# Microcontroller_s_Prephirals_Sheet.net
KiCad netlist of a schematic drawn in Altium Designer
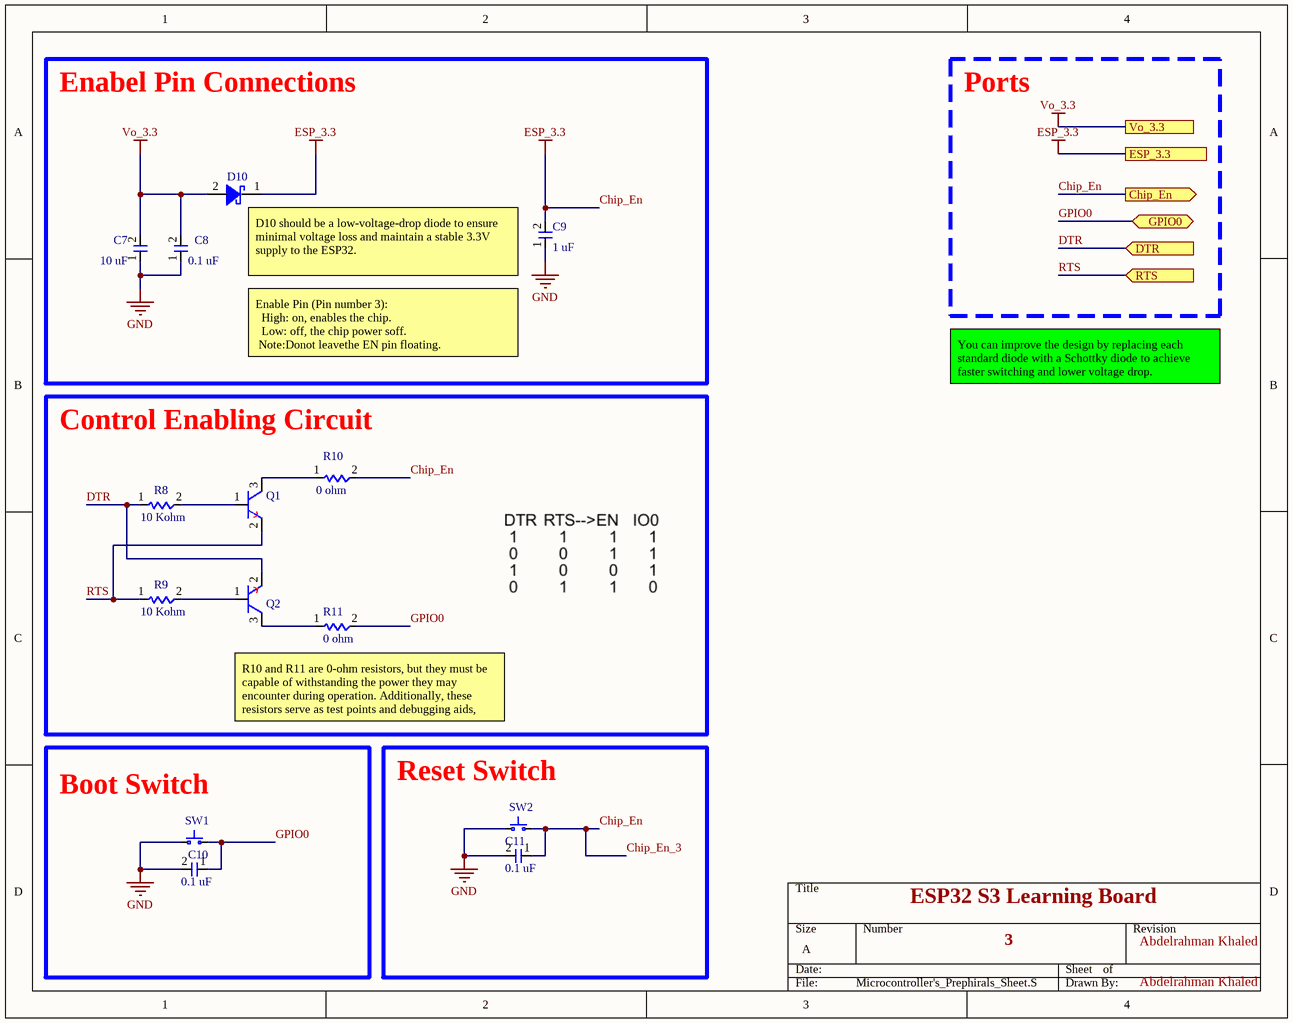
[diagram p0: Microcontroller's_Prephirals_Sheet.SchDoc]

(export (version "E")
  (design (tool "Eeschema 10.0.6"))
  (components
    (comp (ref "C7")
      (value "10 uF")
      (footprint "Capacitor")
      (libsource (lib "ESP32_S3_Integrated_Library") (part "Capacitor"))
    )
    (comp (ref "C8")
      (value "0.1 uF")
      (footprint "Capacitor")
      (libsource (lib "ESP32_S3_Integrated_Library") (part "Capacitor"))
    )
    (comp (ref "C9")
      (value "1 uF")
      (footprint "Capacitor")
      (libsource (lib "ESP32_S3_Integrated_Library") (part "Capacitor"))
    )
    (comp (ref "C10")
      (value "0.1 uF")
      (footprint "Capacitor")
      (libsource (lib "ESP32_S3_Integrated_Library") (part "Capacitor"))
    )
    (comp (ref "C11")
      (value "0.1 uF")
      (footprint "Capacitor")
      (libsource (lib "ESP32_S3_Integrated_Library") (part "Capacitor"))
    )
    (comp (ref "D10")
      (value "0.2V Drop Volt")
      (footprint "Schoktty Diode")
      (description "NRVB120ESFT1G")
      (libsource (lib "ESP32_S3_Integrated_Library") (part "Schottky Diode"))
    )
    (comp (ref "Q1")
      (value "NPN Transistor")
      (footprint "NPN Transistor")
      (description "TRANS PREBIAS NPN 50V TO236AB")
      (libsource (lib "ESP32_S3_Integrated_Library") (part "NPN Transistor"))
    )
    (comp (ref "Q2")
      (value "NPN Transistor")
      (footprint "NPN Transistor")
      (description "TRANS PREBIAS NPN 50V TO236AB")
      (libsource (lib "ESP32_S3_Integrated_Library") (part "NPN Transistor"))
    )
    (comp (ref "R8")
      (value "10 Kohm")
      (footprint "Resistor")
      (libsource (lib "ESP32_S3_Integrated_Library") (part "Resistance"))
    )
    (comp (ref "R9")
      (value "10 Kohm")
      (footprint "Resistor")
      (libsource (lib "ESP32_S3_Integrated_Library") (part "Resistance"))
    )
    (comp (ref "R10")
      (value "0 ohm")
      (footprint "Resistor")
      (libsource (lib "ESP32_S3_Integrated_Library") (part "Resistance"))
    )
    (comp (ref "R11")
      (value "0 ohm")
      (footprint "Resistor")
      (libsource (lib "ESP32_S3_Integrated_Library") (part "Resistance"))
    )
    (comp (ref "SW1")
      (value "Push Button")
      (footprint "Push Button")
      (libsource (lib "ESP32_S3_Integrated_Library") (part "Push Button"))
    )
    (comp (ref "SW2")
      (value "Push Button")
      (footprint "Push Button")
      (libsource (lib "ESP32_S3_Integrated_Library") (part "Push Button"))
    )
  )
  (nets
    (net (code "1") (name "/DTR") (class "Default")
      (node (ref "Q2") (pin "2") (pinfunction "2_2") (pintype "passive"))
      (node (ref "R8") (pin "1") (pinfunction "Pin_1_1") (pintype "passive"))
    )
    (net (code "2") (name "/GPIO0") (class "Default")
      (node (ref "C10") (pin "1") (pinfunction "Pin_1_1") (pintype "passive"))
      (node (ref "R11") (pin "2") (pinfunction "pin_2_2") (pintype "passive"))
      (node (ref "SW1") (pin "2") (pintype "passive"))
    )
    (net (code "3") (name "/RTS") (class "Default")
      (node (ref "Q1") (pin "2") (pinfunction "2_2") (pintype "passive"))
      (node (ref "R9") (pin "1") (pinfunction "Pin_1_1") (pintype "passive"))
    )
    (net (code "4") (name "ESP_3.3") (class "Default")
      (node (ref "C11") (pin "1") (pinfunction "Pin_1_1") (pintype "passive"))
      (node (ref "C9") (pin "2") (pinfunction "Pin_2_2") (pintype "passive"))
      (node (ref "D10") (pin "1") (pintype "passive"))
      (node (ref "R10") (pin "2") (pinfunction "pin_2_2") (pintype "passive"))
      (node (ref "SW2") (pin "2") (pintype "passive"))
    )
    (net (code "5") (name "GND") (class "Default")
      (node (ref "C10") (pin "2") (pinfunction "Pin_2_2") (pintype "passive"))
      (node (ref "C11") (pin "2") (pinfunction "Pin_2_2") (pintype "passive"))
      (node (ref "C7") (pin "1") (pinfunction "Pin_1_1") (pintype "passive"))
      (node (ref "C8") (pin "1") (pinfunction "Pin_1_1") (pintype "passive"))
      (node (ref "C9") (pin "1") (pinfunction "Pin_1_1") (pintype "passive"))
      (node (ref "SW1") (pin "1") (pintype "passive"))
      (node (ref "SW2") (pin "1") (pintype "passive"))
    )
    (net (code "6") (name "Net-(R8-pin_2)") (class "Default")
      (node (ref "Q1") (pin "1") (pinfunction "1_1") (pintype "passive"))
      (node (ref "R8") (pin "2") (pinfunction "pin_2_2") (pintype "passive"))
    )
    (net (code "7") (name "Net-(R9-pin_2)") (class "Default")
      (node (ref "Q2") (pin "1") (pinfunction "1_1") (pintype "passive"))
      (node (ref "R9") (pin "2") (pinfunction "pin_2_2") (pintype "passive"))
    )
    (net (code "8") (name "Net-(R10-Pin_1)") (class "Default")
      (node (ref "Q1") (pin "3") (pinfunction "3_3") (pintype "passive"))
      (node (ref "R10") (pin "1") (pinfunction "Pin_1_1") (pintype "passive"))
    )
    (net (code "9") (name "Net-(R11-Pin_1)") (class "Default")
      (node (ref "Q2") (pin "3") (pinfunction "3_3") (pintype "passive"))
      (node (ref "R11") (pin "1") (pinfunction "Pin_1_1") (pintype "passive"))
    )
    (net (code "10") (name "Vo_3.3") (class "Default")
      (node (ref "C7") (pin "2") (pinfunction "Pin_2_2") (pintype "passive"))
      (node (ref "C8") (pin "2") (pinfunction "Pin_2_2") (pintype "passive"))
      (node (ref "D10") (pin "2") (pintype "passive"))
    )
  )
)
